# DEBUG_UART_INTERFACE.net
KiCad netlist of a schematic drawn in Altium Designer
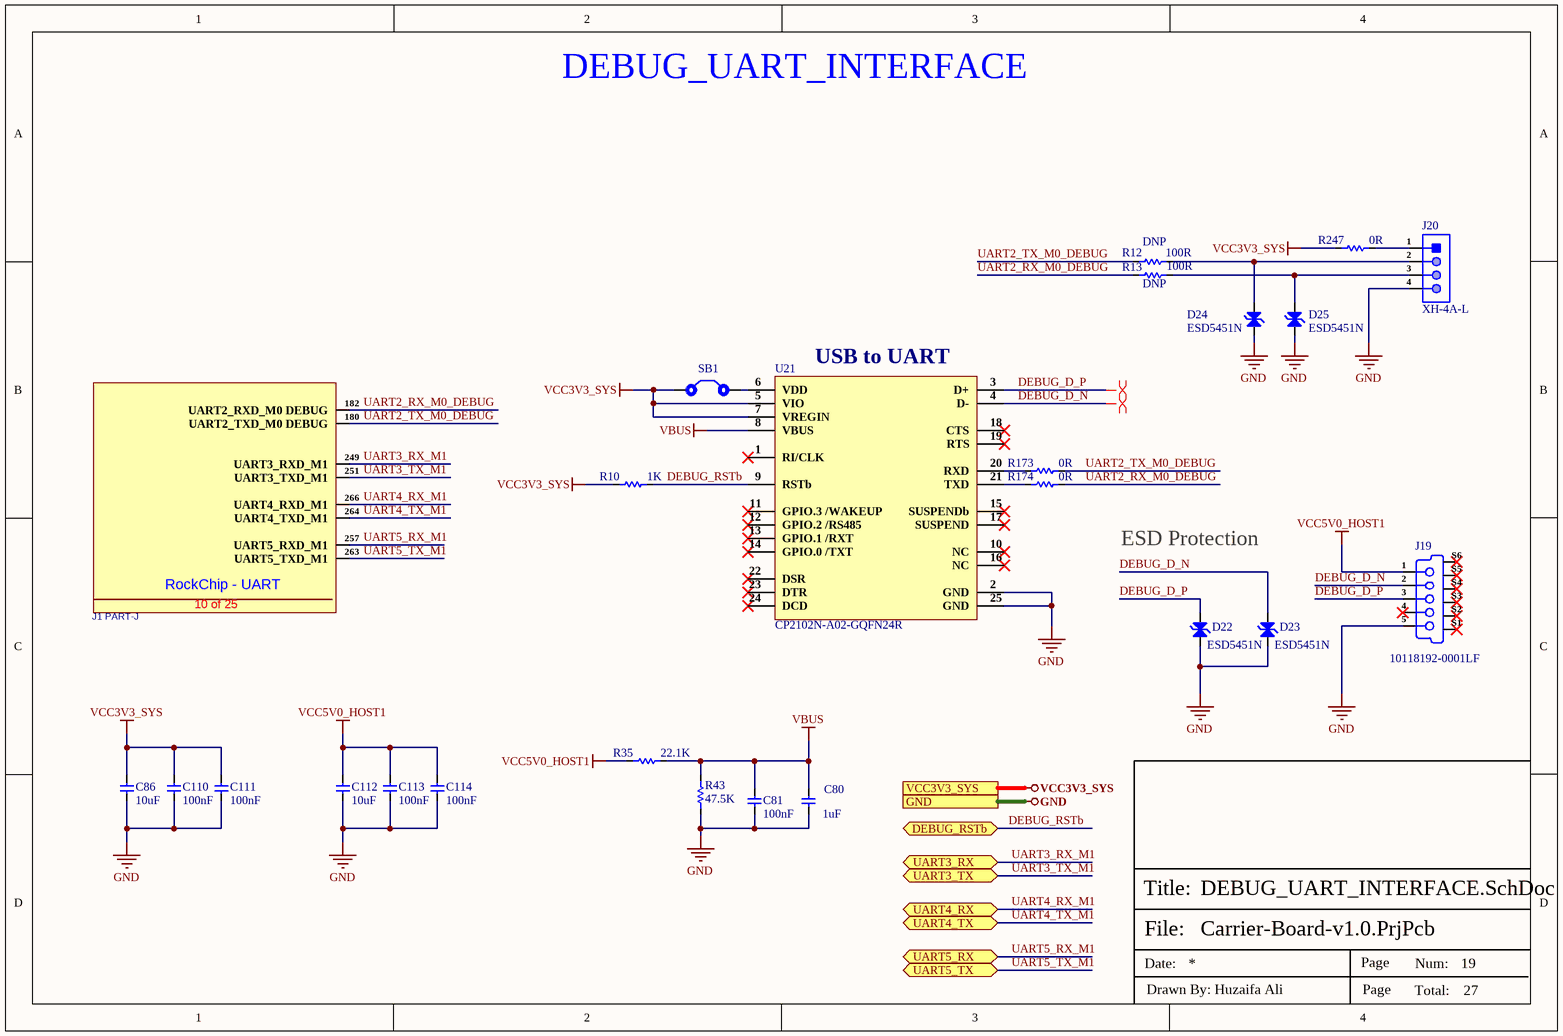
[diagram p0: DEBUG_UART_INTERFACE.SchDoc]

(export (version "E")
  (design (tool "Eeschema 10.0.6"))
  (components
    (comp (ref "C80")
      (value "1uF")
      (footprint "Cap-0402")
      (description "CAP CER 1UF 25V X5R 0402")
      (fields
        (field (name "MANUFACTURER") "Yageo")
        (field (name "MANUFACTURER PART NUMBER") "CC0402KRX5R8BB105")
      )
      (libsource (lib "eSpark Libraries") (part "CC0402KRX5R8BB105"))
    )
    (comp (ref "C81")
      (value "100nF")
      (footprint "Cap-0402")
      (description "CAP CER 0.1UF 16V X5R 0402")
      (fields
        (field (name "MANUFACTURER") "Yageo")
        (field (name "MANUFACTURER PART NUMBER") "CC0402KRX5R7BB104")
      )
      (libsource (lib "eSpark Libraries") (part "CC0402KRX5R7BB104"))
    )
    (comp (ref "C86")
      (value "10uF")
      (footprint "Cap-0603")
      (description "CAP CER 10UF 25V X5R 0603")
      (fields
        (field (name "MANUFACTURER") "TDK")
        (field (name "MANUFACTURER PART NUMBER") "C1608X5R1E106M080AC")
      )
      (libsource (lib "eSpark Libraries") (part "C1608X5R1E106M080AC"))
    )
    (comp (ref "C110")
      (value "100nF")
      (footprint "Cap-0402")
      (description "CAP CER 0.1UF 16V X5R 0402")
      (fields
        (field (name "MANUFACTURER") "Yageo")
        (field (name "MANUFACTURER PART NUMBER") "CC0402KRX5R7BB104")
      )
      (libsource (lib "eSpark Libraries") (part "CC0402KRX5R7BB104"))
    )
    (comp (ref "C111")
      (value "100nF")
      (footprint "Cap-0402")
      (description "CAP CER 0.1UF 16V X5R 0402")
      (fields
        (field (name "MANUFACTURER") "Yageo")
        (field (name "MANUFACTURER PART NUMBER") "CC0402KRX5R7BB104")
      )
      (libsource (lib "eSpark Libraries") (part "CC0402KRX5R7BB104"))
    )
    (comp (ref "C112")
      (value "10uF")
      (footprint "Cap-0603")
      (description "CAP CER 10UF 25V X5R 0603")
      (fields
        (field (name "MANUFACTURER") "TDK")
        (field (name "MANUFACTURER PART NUMBER") "C1608X5R1E106M080AC")
      )
      (libsource (lib "eSpark Libraries") (part "C1608X5R1E106M080AC"))
    )
    (comp (ref "C113")
      (value "100nF")
      (footprint "Cap-0402")
      (description "CAP CER 0.1UF 16V X5R 0402")
      (fields
        (field (name "MANUFACTURER") "Yageo")
        (field (name "MANUFACTURER PART NUMBER") "CC0402KRX5R7BB104")
      )
      (libsource (lib "eSpark Libraries") (part "CC0402KRX5R7BB104"))
    )
    (comp (ref "C114")
      (value "100nF")
      (footprint "Cap-0402")
      (description "CAP CER 0.1UF 16V X5R 0402")
      (fields
        (field (name "MANUFACTURER") "Yageo")
        (field (name "MANUFACTURER PART NUMBER") "CC0402KRX5R7BB104")
      )
      (libsource (lib "eSpark Libraries") (part "CC0402KRX5R7BB104"))
    )
    (comp (ref "D22")
      (value "ESD5451N")
      (footprint "DFN1006-2L (Bi-Directional)")
      (description "DFN1006-2(0402) ESD Protection Devices ROHS")
      (fields (field (name "MANUFACTURER") "TECH PUBLIC") (field (name "LCSC PART NUMBER") "C2936977"))
      (libsource (lib "eSpark Libraries") (part "ESD5451N"))
    )
    (comp (ref "D23")
      (value "ESD5451N")
      (footprint "DFN1006-2L (Bi-Directional)")
      (description "DFN1006-2(0402) ESD Protection Devices ROHS")
      (fields (field (name "MANUFACTURER") "TECH PUBLIC") (field (name "LCSC PART NUMBER") "C2936977"))
      (libsource (lib "eSpark Libraries") (part "ESD5451N"))
    )
    (comp (ref "D24")
      (value "ESD5451N")
      (footprint "DFN1006-2L (Bi-Directional)")
      (description "DFN1006-2(0402) ESD Protection Devices ROHS")
      (fields (field (name "MANUFACTURER") "TECH PUBLIC") (field (name "LCSC PART NUMBER") "C2936977"))
      (libsource (lib "eSpark Libraries") (part "ESD5451N"))
    )
    (comp (ref "D25")
      (value "ESD5451N")
      (footprint "DFN1006-2L (Bi-Directional)")
      (description "DFN1006-2(0402) ESD Protection Devices ROHS")
      (fields (field (name "MANUFACTURER") "TECH PUBLIC") (field (name "LCSC PART NUMBER") "C2936977"))
      (libsource (lib "eSpark Libraries") (part "ESD5451N"))
    )
    (comp (ref "J1 PART-")
      (value "AS0B826-S78B-7H")
      (footprint "AS0B826-S78B-7H")
      (description "SMD,P=0.5mm,Surface Mount，Right Angle")
      (fields (field (name "MANUFACTURER") "FOXCONN") (field (name "LCSC PART NUMBER") "C426232"))
      (libsource (lib "Connector") (part "AS0B826-S78B-7H"))
    )
    (comp (ref "J19")
      (value "10118192-0001LF")
      (footprint "10118192-0001LF_")
      (description "CONN RCPT USB2.0 MICRO B SMD R/A")
      (fields (field (name "MANUFACTURER") "Amphenol FCI") (field (name "LCSC PART NUMBER") "C132564"))
      (libsource (lib "eSpark Libraries") (part "10118192-0001LF"))
    )
    (comp (ref "J20")
      (value "XH-4A-L")
      (footprint "XH-4A-L")
      (description "1x4P 4P XH 1 Tin 2.5mm 4 -25℃~+85℃ Brass 3A Straight Plugin,P=2.5mm Wire To Board Connector ROHS")
      (fields (field (name "MANUFACTURER") "HCTL") (field (name "LCSC PART NUMBER") "C2979569"))
      (libsource (lib "eSpark Libraries") (part "XH-4A-L"))
    )
    (comp (ref "R10")
      (value "1K")
      (footprint "Res-0402")
      (description "RES 1K OHM 1% 1/16W 0402")
      (fields
        (field (name "MANUFACTURER") "Yageo")
        (field (name "MANUFACTURER PART NUMBER") "RC0402FR-071KL")
      )
      (libsource (lib "eSpark Libraries") (part "RC0402FR-071KL"))
    )
    (comp (ref "R12")
      (value "DNP")
      (footprint "Res-0402")
      (description "RES 100 OHM 1% 1/16W 0402")
      (fields
        (field (name "MANUFACTURER") "Yageo")
        (field (name "MANUFACTURER PART NUMBER") "RC0402FR-07100RL")
      )
      (libsource (lib "eSpark Libraries") (part "RC0402FR-07100RL"))
    )
    (comp (ref "R13")
      (value "DNP")
      (footprint "Res-0402")
      (description "RES 100 OHM 1% 1/16W 0402")
      (fields
        (field (name "MANUFACTURER") "Yageo")
        (field (name "MANUFACTURER PART NUMBER") "RC0402FR-07100RL")
      )
      (libsource (lib "eSpark Libraries") (part "RC0402FR-07100RL"))
    )
    (comp (ref "R35")
      (value "22.1K")
      (footprint "Res-0603")
      (description "RES 22.1K OHM 1% 1/10W 0603")
      (fields
        (field (name "MANUFACTURER") "Yageo")
        (field (name "MANUFACTURER PART NUMBER") "RC0603FR-0722K1L")
      )
      (libsource (lib "eSpark Libraries") (part "RC0603FR-0722K1L"))
    )
    (comp (ref "R43")
      (value "47.5K")
      (footprint "Res-0603")
      (description "RES 47.5K OHM 1% 1/10W 0603")
      (fields
        (field (name "MANUFACTURER") "Yageo")
        (field (name "MANUFACTURER PART NUMBER") "RC0603FR-0747K5L")
      )
      (libsource (lib "eSpark Libraries") (part "RC0603FR-0747K5L"))
    )
    (comp (ref "R173")
      (value "0R")
      (footprint "Res-0402")
      (description "RES 0 OHM JUMPER 1/16W 0402")
      (fields
        (field (name "MANUFACTURER") "Yageo")
        (field (name "MANUFACTURER PART NUMBER") "RC0402FR-070RL")
      )
      (libsource (lib "eSpark Libraries") (part "RC0402FR-070RL"))
    )
    (comp (ref "R174")
      (value "0R")
      (footprint "Res-0402")
      (description "RES 0 OHM JUMPER 1/16W 0402")
      (fields
        (field (name "MANUFACTURER") "Yageo")
        (field (name "MANUFACTURER PART NUMBER") "RC0402FR-070RL")
      )
      (libsource (lib "eSpark Libraries") (part "RC0402FR-070RL"))
    )
    (comp (ref "R247")
      (value "0R")
      (footprint "Res-0402")
      (description "RES 0 OHM JUMPER 1/16W 0402")
      (fields
        (field (name "MANUFACTURER") "Yageo")
        (field (name "MANUFACTURER PART NUMBER") "RC0402FR-070RL")
      )
      (libsource (lib "eSpark Libraries") (part "RC0402FR-070RL"))
    )
    (comp (ref "SB1")
      (value "Solder Bridge 0402")
      (footprint "Solder Bridge 0402")
      (description "Solder Bridge ON")
      (libsource (lib "eSpark Libraries") (part "Solder Bridge 0402"))
    )
    (comp (ref "U21")
      (value "CP2102N-A02-GQFN24R")
      (footprint "CP2102N-A02-GQFN24R")
      (description "IC USB TO UART BRIDGE QFN24")
      (fields (field (name "MANUFACTURER") "Silicon Labs"))
      (libsource (lib "Jude_permall") (part "CP2102N-A02-GQFN24R"))
    )
  )
  (nets
    (net (code "1") (name "/DEBUG_D_N") (class "Default")
      (node (ref "D23") (pin "2") (pinfunction "K_2") (pintype "passive"))
      (node (ref "J19") (pin "2") (pinfunction "D-_2") (pintype "passive"))
      (node (ref "U21") (pin "4") (pinfunction "D-_4") (pintype "passive"))
    )
    (net (code "2") (name "/DEBUG_D_P") (class "Default")
      (node (ref "D22") (pin "2") (pinfunction "K_2") (pintype "passive"))
      (node (ref "J19") (pin "3") (pinfunction "D+_3") (pintype "passive"))
      (node (ref "U21") (pin "3") (pinfunction "D+_3") (pintype "passive"))
    )
    (net (code "3") (name "/DEBUG_RSTb") (class "Default")
      (node (ref "R10") (pin "2") (pinfunction "2_2") (pintype "passive"))
      (node (ref "U21") (pin "9") (pinfunction "RSTb_9") (pintype "passive"))
    )
    (net (code "4") (name "/UART2_RX_M0_DEBUG") (class "Default")
      (node (ref "J1 PART-") (pin "182") (pinfunction "UART2_RXD_M0_DEBUG_182") (pintype "passive"))
      (node (ref "R13") (pin "1") (pinfunction "1_1") (pintype "passive"))
      (node (ref "R174") (pin "2") (pinfunction "2_2") (pintype "passive"))
    )
    (net (code "5") (name "/UART2_TX_M0_DEBUG") (class "Default")
      (node (ref "J1 PART-") (pin "180") (pinfunction "UART2_TXD_M0_DEBUG_180") (pintype "passive"))
      (node (ref "R12") (pin "1") (pinfunction "1_1") (pintype "passive"))
      (node (ref "R173") (pin "2") (pinfunction "2_2") (pintype "passive"))
    )
    (net (code "6") (name "/UART3_RX_M1") (class "Default")
      (node (ref "J1 PART-") (pin "249") (pinfunction "UART3_RXD_M1_249") (pintype "passive"))
    )
    (net (code "7") (name "/UART3_TX_M1") (class "Default")
      (node (ref "J1 PART-") (pin "251") (pinfunction "UART3_TXD_M1_251") (pintype "passive"))
    )
    (net (code "8") (name "/UART4_RX_M1") (class "Default")
      (node (ref "J1 PART-") (pin "266") (pinfunction "UART4_RXD_M1_266") (pintype "passive"))
    )
    (net (code "9") (name "/UART4_TX_M1") (class "Default")
      (node (ref "J1 PART-") (pin "264") (pinfunction "UART4_TXD_M1_264") (pintype "passive"))
    )
    (net (code "10") (name "/UART5_RX_M1") (class "Default")
      (node (ref "J1 PART-") (pin "257") (pinfunction "UART5_RXD_M1_257") (pintype "passive"))
    )
    (net (code "11") (name "/UART5_TX_M1") (class "Default")
      (node (ref "J1 PART-") (pin "263") (pinfunction "UART5_TXD_M1_263") (pintype "passive"))
    )
    (net (code "12") (name "GND") (class "Default")
      (node (ref "C110") (pin "1") (pinfunction "1_1") (pintype "passive"))
      (node (ref "C111") (pin "1") (pinfunction "1_1") (pintype "passive"))
      (node (ref "C112") (pin "1") (pinfunction "1_1") (pintype "passive"))
      (node (ref "C113") (pin "1") (pinfunction "1_1") (pintype "passive"))
      (node (ref "C114") (pin "1") (pinfunction "1_1") (pintype "passive"))
      (node (ref "C80") (pin "2") (pinfunction "2_2") (pintype "passive"))
      (node (ref "C81") (pin "2") (pinfunction "2_2") (pintype "passive"))
      (node (ref "C86") (pin "1") (pinfunction "1_1") (pintype "passive"))
      (node (ref "D22") (pin "1") (pinfunction "K_1") (pintype "passive"))
      (node (ref "D23") (pin "1") (pinfunction "K_1") (pintype "passive"))
      (node (ref "D24") (pin "1") (pinfunction "K_1") (pintype "passive"))
      (node (ref "D25") (pin "1") (pinfunction "K_1") (pintype "passive"))
      (node (ref "J19") (pin "5") (pinfunction "GND_5") (pintype "passive"))
      (node (ref "J20") (pin "4") (pinfunction "4_4") (pintype "passive"))
      (node (ref "R43") (pin "2") (pinfunction "2_2") (pintype "passive"))
      (node (ref "U21") (pin "2") (pinfunction "GND_2") (pintype "passive"))
      (node (ref "U21") (pin "25") (pinfunction "GND_25") (pintype "passive"))
    )
    (net (code "13") (name "Net-(D24-K-Pad2)") (class "Default")
      (node (ref "D24") (pin "2") (pinfunction "K_2") (pintype "passive"))
      (node (ref "J20") (pin "2") (pinfunction "2_2") (pintype "passive"))
      (node (ref "R12") (pin "2") (pinfunction "2_2") (pintype "passive"))
    )
    (net (code "14") (name "Net-(D25-K-Pad2)") (class "Default")
      (node (ref "D25") (pin "2") (pinfunction "K_2") (pintype "passive"))
      (node (ref "J20") (pin "3") (pinfunction "3_3") (pintype "passive"))
      (node (ref "R13") (pin "2") (pinfunction "2_2") (pintype "passive"))
    )
    (net (code "15") (name "Net-(J20-Pad1)") (class "Default")
      (node (ref "J20") (pin "1") (pinfunction "1_1") (pintype "passive"))
      (node (ref "R247") (pin "2") (pinfunction "2_2") (pintype "passive"))
    )
    (net (code "16") (name "Net-(U21-RXD)") (class "Default")
      (node (ref "R173") (pin "1") (pinfunction "1_1") (pintype "passive"))
      (node (ref "U21") (pin "20") (pinfunction "RXD_20") (pintype "passive"))
    )
    (net (code "17") (name "Net-(U21-TXD)") (class "Default")
      (node (ref "R174") (pin "1") (pinfunction "1_1") (pintype "passive"))
      (node (ref "U21") (pin "21") (pinfunction "TXD_21") (pintype "passive"))
    )
    (net (code "18") (name "Net-(U21-VDD)") (class "Default")
      (node (ref "SB1") (pin "2") (pinfunction "2_2") (pintype "passive"))
      (node (ref "U21") (pin "6") (pinfunction "VDD_6") (pintype "passive"))
    )
    (net (code "19") (name "VBUS") (class "Default")
      (node (ref "C80") (pin "1") (pinfunction "1_1") (pintype "passive"))
      (node (ref "C81") (pin "1") (pinfunction "1_1") (pintype "passive"))
      (node (ref "R35") (pin "2") (pinfunction "2_2") (pintype "passive"))
      (node (ref "R43") (pin "1") (pinfunction "1_1") (pintype "passive"))
      (node (ref "U21") (pin "8") (pinfunction "VBUS_8") (pintype "passive"))
    )
    (net (code "20") (name "VCC3V3_SYS") (class "Default")
      (node (ref "C110") (pin "2") (pinfunction "2_2") (pintype "passive"))
      (node (ref "C111") (pin "2") (pinfunction "2_2") (pintype "passive"))
      (node (ref "C86") (pin "2") (pinfunction "2_2") (pintype "passive"))
      (node (ref "R10") (pin "1") (pinfunction "1_1") (pintype "passive"))
      (node (ref "R247") (pin "1") (pinfunction "1_1") (pintype "passive"))
      (node (ref "SB1") (pin "1") (pinfunction "1_1") (pintype "passive"))
      (node (ref "U21") (pin "5") (pinfunction "VIO_5") (pintype "passive"))
      (node (ref "U21") (pin "7") (pinfunction "VREGIN_7") (pintype "passive"))
    )
    (net (code "21") (name "VCC5V0_HOST1") (class "Default")
      (node (ref "C112") (pin "2") (pinfunction "2_2") (pintype "passive"))
      (node (ref "C113") (pin "2") (pinfunction "2_2") (pintype "passive"))
      (node (ref "C114") (pin "2") (pinfunction "2_2") (pintype "passive"))
      (node (ref "J19") (pin "1") (pinfunction "V_BUS_(5V)_1") (pintype "passive"))
      (node (ref "R35") (pin "1") (pinfunction "1_1") (pintype "passive"))
    )
    (net (code "22") (name "unconnected-(J19-NC-Pad4)") (class "Default")
      (node (ref "J19") (pin "4") (pinfunction "NC_4") (pintype "passive+no_connect"))
    )
    (net (code "23") (name "unconnected-(J19-Shield-PadS1)") (class "Default")
      (node (ref "J19") (pin "S1") (pinfunction "Shield_S1") (pintype "passive+no_connect"))
    )
    (net (code "24") (name "unconnected-(J19-Shield-PadS2)") (class "Default")
      (node (ref "J19") (pin "S2") (pinfunction "Shield_S2") (pintype "passive+no_connect"))
    )
    (net (code "25") (name "unconnected-(J19-Shield-PadS3)") (class "Default")
      (node (ref "J19") (pin "S3") (pinfunction "Shield_S3") (pintype "passive+no_connect"))
    )
    (net (code "26") (name "unconnected-(J19-Shield-PadS4)") (class "Default")
      (node (ref "J19") (pin "S4") (pinfunction "Shield_S4") (pintype "passive+no_connect"))
    )
    (net (code "27") (name "unconnected-(J19-Shield-PadS5)") (class "Default")
      (node (ref "J19") (pin "S5") (pinfunction "Shield_S5") (pintype "passive+no_connect"))
    )
    (net (code "28") (name "unconnected-(J19-Shield-PadS6)") (class "Default")
      (node (ref "J19") (pin "S6") (pinfunction "Shield_S6") (pintype "passive+no_connect"))
    )
    (net (code "29") (name "unconnected-(U21-CTS-Pad18)") (class "Default")
      (node (ref "U21") (pin "18") (pinfunction "CTS_18") (pintype "passive+no_connect"))
    )
    (net (code "30") (name "unconnected-(U21-DCD-Pad24)") (class "Default")
      (node (ref "U21") (pin "24") (pinfunction "DCD_24") (pintype "passive+no_connect"))
    )
    (net (code "31") (name "unconnected-(U21-DSR-Pad22)") (class "Default")
      (node (ref "U21") (pin "22") (pinfunction "DSR_22") (pintype "passive+no_connect"))
    )
    (net (code "32") (name "unconnected-(U21-DTR-Pad23)") (class "Default")
      (node (ref "U21") (pin "23") (pinfunction "DTR_23") (pintype "passive+no_connect"))
    )
    (net (code "33") (name "unconnected-(U21-GPIO.0_{slash}TXT-Pad14)") (class "Default")
      (node (ref "U21") (pin "14") (pinfunction "GPIO.0_/TXT_14") (pintype "passive+no_connect"))
    )
    (net (code "34") (name "unconnected-(U21-GPIO.1_{slash}RXT-Pad13)") (class "Default")
      (node (ref "U21") (pin "13") (pinfunction "GPIO.1_/RXT_13") (pintype "passive+no_connect"))
    )
    (net (code "35") (name "unconnected-(U21-GPIO.2_{slash}RS485-Pad12)") (class "Default")
      (node (ref "U21") (pin "12") (pinfunction "GPIO.2_/RS485_12") (pintype "passive+no_connect"))
    )
    (net (code "36") (name "unconnected-(U21-GPIO.3_{slash}WAKEUP-Pad11)") (class "Default")
      (node (ref "U21") (pin "11") (pinfunction "GPIO.3_/WAKEUP_11") (pintype "passive+no_connect"))
    )
    (net (code "37") (name "unconnected-(U21-NC-Pad10)") (class "Default")
      (node (ref "U21") (pin "10") (pinfunction "NC_10") (pintype "passive+no_connect"))
    )
    (net (code "38") (name "unconnected-(U21-NC-Pad16)") (class "Default")
      (node (ref "U21") (pin "16") (pinfunction "NC_16") (pintype "passive+no_connect"))
    )
    (net (code "39") (name "unconnected-(U21-RI{slash}CLK-Pad1)") (class "Default")
      (node (ref "U21") (pin "1") (pinfunction "RI/CLK_1") (pintype "passive+no_connect"))
    )
    (net (code "40") (name "unconnected-(U21-RTS-Pad19)") (class "Default")
      (node (ref "U21") (pin "19") (pinfunction "RTS_19") (pintype "passive+no_connect"))
    )
    (net (code "41") (name "unconnected-(U21-SUSPEND-Pad17)") (class "Default")
      (node (ref "U21") (pin "17") (pinfunction "SUSPEND_17") (pintype "passive+no_connect"))
    )
    (net (code "42") (name "unconnected-(U21-SUSPENDb-Pad15)") (class "Default")
      (node (ref "U21") (pin "15") (pinfunction "SUSPENDb_15") (pintype "passive+no_connect"))
    )
  )
)
